# sch_propeller.net
KiCad netlist of a schematic drawn in Altium Designer
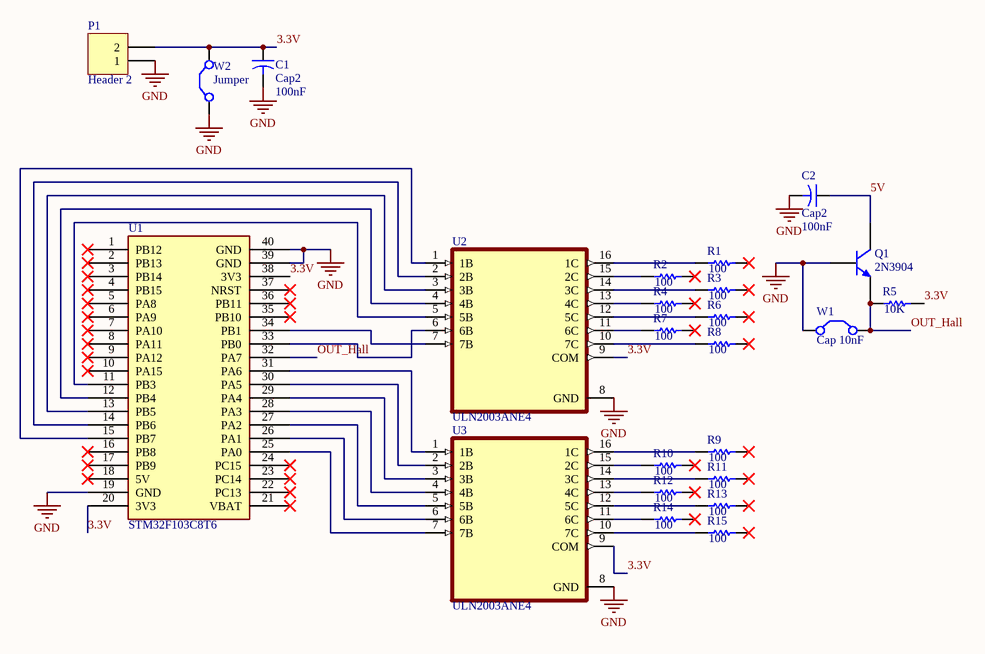
[diagram p0: sch_propeller.SchDoc]

(export (version "E")
  (design (tool "Eeschema 10.0.6"))
  (components
    (comp (ref "C1")
      (value "Cap2")
      (footprint "CAPR5-4X5")
      (description "Capacitor")
      (fields (field (name "ALTIUM_VALUE") "100nF") (field (name "PUBLISHER") "Altium Limited"))
      (libsource (lib "Miscellaneous Devices") (part "Cap2"))
    )
    (comp (ref "C2")
      (value "Cap2")
      (footprint "CAPR5-4X5")
      (description "Capacitor")
      (fields (field (name "ALTIUM_VALUE") "100nF") (field (name "PUBLISHER") "Altium Limited"))
      (libsource (lib "Miscellaneous Devices") (part "Cap2"))
    )
    (comp (ref "P1")
      (value "Header 2")
      (footprint "HDR1X2")
      (description "Header, 2-Pin")
      (fields (field (name "PUBLISHER") "Altium Limited"))
      (libsource (lib "Miscellaneous Connectors") (part "Header 2"))
    )
    (comp (ref "Q1")
      (value "2N3904")
      (footprint "TO-92A")
      (description "NPN General Purpose Amplifier")
      (fields (field (name "PUBLISHER") "Altium Limited"))
      (libsource (lib "Miscellaneous Devices") (part "2N3904"))
    )
    (comp (ref "R1")
      (value "100")
      (footprint "AXIAL-0.3")
      (description "Resistor")
      (fields (field (name "Comment") "Res1") (field (name "PUBLISHER") "Altium Limited"))
      (libsource (lib "Miscellaneous Devices") (part "Res1"))
    )
    (comp (ref "R2")
      (value "100")
      (footprint "AXIAL-0.3")
      (description "Resistor")
      (fields (field (name "Comment") "Res1") (field (name "PUBLISHER") "Altium Limited"))
      (libsource (lib "Miscellaneous Devices") (part "Res1"))
    )
    (comp (ref "R3")
      (value "100")
      (footprint "AXIAL-0.3")
      (description "Resistor")
      (fields (field (name "Comment") "Res1") (field (name "PUBLISHER") "Altium Limited"))
      (libsource (lib "Miscellaneous Devices") (part "Res1"))
    )
    (comp (ref "R4")
      (value "100")
      (footprint "AXIAL-0.3")
      (description "Resistor")
      (fields (field (name "Comment") "Res1") (field (name "PUBLISHER") "Altium Limited"))
      (libsource (lib "Miscellaneous Devices") (part "Res1"))
    )
    (comp (ref "R5")
      (value "10K")
      (footprint "AXIAL-0.3")
      (description "Resistor")
      (fields (field (name "Comment") "Res1") (field (name "PUBLISHER") "Altium Limited"))
      (libsource (lib "Miscellaneous Devices") (part "Res1"))
    )
    (comp (ref "R6")
      (value "100")
      (footprint "AXIAL-0.3")
      (description "Resistor")
      (fields (field (name "Comment") "Res1") (field (name "PUBLISHER") "Altium Limited"))
      (libsource (lib "Miscellaneous Devices") (part "Res1"))
    )
    (comp (ref "R7")
      (value "100")
      (footprint "AXIAL-0.3")
      (description "Resistor")
      (fields (field (name "Comment") "Res1") (field (name "PUBLISHER") "Altium Limited"))
      (libsource (lib "Miscellaneous Devices") (part "Res1"))
    )
    (comp (ref "R8")
      (value "100")
      (footprint "AXIAL-0.3")
      (description "Resistor")
      (fields (field (name "Comment") "Res1") (field (name "PUBLISHER") "Altium Limited"))
      (libsource (lib "Miscellaneous Devices") (part "Res1"))
    )
    (comp (ref "R9")
      (value "100")
      (footprint "AXIAL-0.3")
      (description "Resistor")
      (fields (field (name "Comment") "Res1") (field (name "PUBLISHER") "Altium Limited"))
      (libsource (lib "Miscellaneous Devices") (part "Res1"))
    )
    (comp (ref "R10")
      (value "100")
      (footprint "AXIAL-0.3")
      (description "Resistor")
      (fields (field (name "Comment") "Res1") (field (name "PUBLISHER") "Altium Limited"))
      (libsource (lib "Miscellaneous Devices") (part "Res1"))
    )
    (comp (ref "R11")
      (value "100")
      (footprint "AXIAL-0.3")
      (description "Resistor")
      (fields (field (name "Comment") "Res1") (field (name "PUBLISHER") "Altium Limited"))
      (libsource (lib "Miscellaneous Devices") (part "Res1"))
    )
    (comp (ref "R12")
      (value "100")
      (footprint "AXIAL-0.3")
      (description "Resistor")
      (fields (field (name "Comment") "Res1") (field (name "PUBLISHER") "Altium Limited"))
      (libsource (lib "Miscellaneous Devices") (part "Res1"))
    )
    (comp (ref "R13")
      (value "100")
      (footprint "AXIAL-0.3")
      (description "Resistor")
      (fields (field (name "Comment") "Res1") (field (name "PUBLISHER") "Altium Limited"))
      (libsource (lib "Miscellaneous Devices") (part "Res1"))
    )
    (comp (ref "R14")
      (value "100")
      (footprint "AXIAL-0.3")
      (description "Resistor")
      (fields (field (name "Comment") "Res1") (field (name "PUBLISHER") "Altium Limited"))
      (libsource (lib "Miscellaneous Devices") (part "Res1"))
    )
    (comp (ref "R15")
      (value "100")
      (footprint "AXIAL-0.3")
      (description "Resistor")
      (fields (field (name "Comment") "Res1") (field (name "PUBLISHER") "Altium Limited"))
      (libsource (lib "Miscellaneous Devices") (part "Res1"))
    )
    (comp (ref "U1")
      (value "STM32F103C8T6")
      (footprint "Stm32 BluePill")
      (description "Designed By @Alixahedi")
      (libsource (lib "Stm32 Blue Pill") (part "BluePill"))
    )
    (comp (ref "U2")
      (value "ULN2003ANE4")
      (footprint "DIP794W45P254L1969H508Q16")
      (description "50-V, 7-ch darlington transistor array, -20C to 70C")
      (fields (field (name "MF") "Texas Instruments"))
      (libsource (lib "ULN2003ANE4") (part "ULN2003ANE4"))
    )
    (comp (ref "U3")
      (value "ULN2003ANE4")
      (footprint "DIP794W45P254L1969H508Q16")
      (description "50-V, 7-ch darlington transistor array, -20C to 70C")
      (fields (field (name "MF") "Texas Instruments"))
      (libsource (lib "ULN2003ANE4") (part "ULN2003ANE4"))
    )
    (comp (ref "W1")
      (value "Cap 10nF")
      (footprint "RAD-0.2")
      (description "Jumper Wire")
      (fields (field (name "PUBLISHER") "Altium Limited"))
      (libsource (lib "Miscellaneous Devices") (part "Jumper"))
    )
    (comp (ref "W2")
      (value "Jumper")
      (footprint "RAD-0.2")
      (description "Jumper Wire")
      (fields (field (name "PUBLISHER") "Altium Limited"))
      (libsource (lib "Miscellaneous Devices") (part "Jumper"))
    )
  )
  (nets
    (net (code "1") (name "/3.3V") (class "Default")
      (node (ref "C1") (pin "1") (pinfunction "1_1") (pintype "passive"))
      (node (ref "P1") (pin "2") (pinfunction "2_2") (pintype "passive"))
      (node (ref "R5") (pin "2") (pinfunction "2_2") (pintype "passive"))
      (node (ref "U1") (pin "20") (pinfunction "3V3_20") (pintype "passive"))
      (node (ref "U1") (pin "38") (pinfunction "3V3_38") (pintype "passive"))
      (node (ref "U2") (pin "9") (pinfunction "COM_9") (pintype "output"))
      (node (ref "U3") (pin "9") (pinfunction "COM_9") (pintype "output"))
      (node (ref "W2") (pin "2") (pinfunction "C2_2") (pintype "passive"))
    )
    (net (code "2") (name "/5V") (class "Default")
      (node (ref "C2") (pin "1") (pinfunction "1_1") (pintype "passive"))
      (node (ref "Q1") (pin "3") (pinfunction "C_3") (pintype "passive"))
    )
    (net (code "3") (name "/OUT_Hall") (class "Default")
      (node (ref "Q1") (pin "1") (pinfunction "E_1") (pintype "passive"))
      (node (ref "R5") (pin "1") (pinfunction "1_1") (pintype "passive"))
      (node (ref "U1") (pin "32") (pinfunction "PA7_32") (pintype "passive"))
      (node (ref "W1") (pin "2") (pinfunction "C2_2") (pintype "passive"))
    )
    (net (code "4") (name "GND") (class "Default")
      (node (ref "C1") (pin "2") (pinfunction "2_2") (pintype "passive"))
      (node (ref "C2") (pin "2") (pinfunction "2_2") (pintype "passive"))
      (node (ref "P1") (pin "1") (pinfunction "1_1") (pintype "passive"))
      (node (ref "Q1") (pin "2") (pinfunction "B_2") (pintype "passive"))
      (node (ref "U1") (pin "19") (pinfunction "GND_19") (pintype "passive"))
      (node (ref "U1") (pin "39") (pinfunction "GND_39") (pintype "passive"))
      (node (ref "U1") (pin "40") (pinfunction "GND_40") (pintype "passive"))
      (node (ref "U2") (pin "8") (pinfunction "GND_8") (pintype "power_in"))
      (node (ref "U3") (pin "8") (pinfunction "GND_8") (pintype "power_in"))
      (node (ref "W1") (pin "1") (pinfunction "C1_1") (pintype "passive"))
      (node (ref "W2") (pin "1") (pinfunction "C1_1") (pintype "passive"))
    )
    (net (code "5") (name "Net-(U1-PA0)") (class "Default")
      (node (ref "U1") (pin "25") (pinfunction "PA0_25") (pintype "passive"))
      (node (ref "U3") (pin "7") (pinfunction "7B_7") (pintype "input"))
    )
    (net (code "6") (name "Net-(U1-PA1)") (class "Default")
      (node (ref "U1") (pin "26") (pinfunction "PA1_26") (pintype "passive"))
      (node (ref "U3") (pin "6") (pinfunction "6B_6") (pintype "input"))
    )
    (net (code "7") (name "Net-(U1-PA2)") (class "Default")
      (node (ref "U1") (pin "27") (pinfunction "PA2_27") (pintype "passive"))
      (node (ref "U3") (pin "5") (pinfunction "5B_5") (pintype "input"))
    )
    (net (code "8") (name "Net-(U1-PA3)") (class "Default")
      (node (ref "U1") (pin "28") (pinfunction "PA3_28") (pintype "passive"))
      (node (ref "U3") (pin "4") (pinfunction "4B_4") (pintype "input"))
    )
    (net (code "9") (name "Net-(U1-PA4)") (class "Default")
      (node (ref "U1") (pin "29") (pinfunction "PA4_29") (pintype "passive"))
      (node (ref "U3") (pin "3") (pinfunction "3B_3") (pintype "input"))
    )
    (net (code "10") (name "Net-(U1-PA5)") (class "Default")
      (node (ref "U1") (pin "30") (pinfunction "PA5_30") (pintype "passive"))
      (node (ref "U3") (pin "2") (pinfunction "2B_2") (pintype "input"))
    )
    (net (code "11") (name "Net-(U1-PA6)") (class "Default")
      (node (ref "U1") (pin "31") (pinfunction "PA6_31") (pintype "passive"))
      (node (ref "U3") (pin "1") (pinfunction "1B_1") (pintype "input"))
    )
    (net (code "12") (name "Net-(U1-PB0)") (class "Default")
      (node (ref "U1") (pin "33") (pinfunction "PB0_33") (pintype "passive"))
      (node (ref "U2") (pin "6") (pinfunction "6B_6") (pintype "input"))
    )
    (net (code "13") (name "Net-(U1-PB1)") (class "Default")
      (node (ref "U1") (pin "34") (pinfunction "PB1_34") (pintype "passive"))
      (node (ref "U2") (pin "7") (pinfunction "7B_7") (pintype "input"))
    )
    (net (code "14") (name "Net-(U1-PB3)") (class "Default")
      (node (ref "U1") (pin "11") (pinfunction "PB3_11") (pintype "passive"))
      (node (ref "U2") (pin "5") (pinfunction "5B_5") (pintype "input"))
    )
    (net (code "15") (name "Net-(U1-PB4)") (class "Default")
      (node (ref "U1") (pin "12") (pinfunction "PB4_12") (pintype "passive"))
      (node (ref "U2") (pin "4") (pinfunction "4B_4") (pintype "input"))
    )
    (net (code "16") (name "Net-(U1-PB5)") (class "Default")
      (node (ref "U1") (pin "13") (pinfunction "PB5_13") (pintype "passive"))
      (node (ref "U2") (pin "3") (pinfunction "3B_3") (pintype "input"))
    )
    (net (code "17") (name "Net-(U1-PB6)") (class "Default")
      (node (ref "U1") (pin "14") (pinfunction "PB6_14") (pintype "passive"))
      (node (ref "U2") (pin "2") (pinfunction "2B_2") (pintype "input"))
    )
    (net (code "18") (name "Net-(U1-PB7)") (class "Default")
      (node (ref "U1") (pin "15") (pinfunction "PB7_15") (pintype "passive"))
      (node (ref "U2") (pin "1") (pinfunction "1B_1") (pintype "input"))
    )
    (net (code "19") (name "Net-(U2-1C)") (class "Default")
      (node (ref "R1") (pin "1") (pinfunction "1_1") (pintype "passive"))
      (node (ref "U2") (pin "16") (pinfunction "1C_16") (pintype "output"))
    )
    (net (code "20") (name "Net-(U2-2C)") (class "Default")
      (node (ref "R2") (pin "1") (pinfunction "1_1") (pintype "passive"))
      (node (ref "U2") (pin "15") (pinfunction "2C_15") (pintype "output"))
    )
    (net (code "21") (name "Net-(U2-3C)") (class "Default")
      (node (ref "R3") (pin "1") (pinfunction "1_1") (pintype "passive"))
      (node (ref "U2") (pin "14") (pinfunction "3C_14") (pintype "output"))
    )
    (net (code "22") (name "Net-(U2-4C)") (class "Default")
      (node (ref "R4") (pin "1") (pinfunction "1_1") (pintype "passive"))
      (node (ref "U2") (pin "13") (pinfunction "4C_13") (pintype "output"))
    )
    (net (code "23") (name "Net-(U2-5C)") (class "Default")
      (node (ref "R6") (pin "1") (pinfunction "1_1") (pintype "passive"))
      (node (ref "U2") (pin "12") (pinfunction "5C_12") (pintype "output"))
    )
    (net (code "24") (name "Net-(U2-6C)") (class "Default")
      (node (ref "R7") (pin "1") (pinfunction "1_1") (pintype "passive"))
      (node (ref "U2") (pin "11") (pinfunction "6C_11") (pintype "output"))
    )
    (net (code "25") (name "Net-(U2-7C)") (class "Default")
      (node (ref "R8") (pin "1") (pinfunction "1_1") (pintype "passive"))
      (node (ref "U2") (pin "10") (pinfunction "7C_10") (pintype "output"))
    )
    (net (code "26") (name "Net-(U3-1C)") (class "Default")
      (node (ref "R9") (pin "1") (pinfunction "1_1") (pintype "passive"))
      (node (ref "U3") (pin "16") (pinfunction "1C_16") (pintype "output"))
    )
    (net (code "27") (name "Net-(U3-2C)") (class "Default")
      (node (ref "R10") (pin "1") (pinfunction "1_1") (pintype "passive"))
      (node (ref "U3") (pin "15") (pinfunction "2C_15") (pintype "output"))
    )
    (net (code "28") (name "Net-(U3-3C)") (class "Default")
      (node (ref "R11") (pin "1") (pinfunction "1_1") (pintype "passive"))
      (node (ref "U3") (pin "14") (pinfunction "3C_14") (pintype "output"))
    )
    (net (code "29") (name "Net-(U3-4C)") (class "Default")
      (node (ref "R12") (pin "1") (pinfunction "1_1") (pintype "passive"))
      (node (ref "U3") (pin "13") (pinfunction "4C_13") (pintype "output"))
    )
    (net (code "30") (name "Net-(U3-5C)") (class "Default")
      (node (ref "R13") (pin "1") (pinfunction "1_1") (pintype "passive"))
      (node (ref "U3") (pin "12") (pinfunction "5C_12") (pintype "output"))
    )
    (net (code "31") (name "Net-(U3-6C)") (class "Default")
      (node (ref "R14") (pin "1") (pinfunction "1_1") (pintype "passive"))
      (node (ref "U3") (pin "11") (pinfunction "6C_11") (pintype "output"))
    )
    (net (code "32") (name "Net-(U3-7C)") (class "Default")
      (node (ref "R15") (pin "1") (pinfunction "1_1") (pintype "passive"))
      (node (ref "U3") (pin "10") (pinfunction "7C_10") (pintype "output"))
    )
    (net (code "33") (name "unconnected-(R1-Pad2)") (class "Default")
      (node (ref "R1") (pin "2") (pinfunction "2_2") (pintype "passive+no_connect"))
    )
    (net (code "34") (name "unconnected-(R2-Pad2)") (class "Default")
      (node (ref "R2") (pin "2") (pinfunction "2_2") (pintype "passive+no_connect"))
    )
    (net (code "35") (name "unconnected-(R3-Pad2)") (class "Default")
      (node (ref "R3") (pin "2") (pinfunction "2_2") (pintype "passive+no_connect"))
    )
    (net (code "36") (name "unconnected-(R4-Pad2)") (class "Default")
      (node (ref "R4") (pin "2") (pinfunction "2_2") (pintype "passive+no_connect"))
    )
    (net (code "37") (name "unconnected-(R6-Pad2)") (class "Default")
      (node (ref "R6") (pin "2") (pinfunction "2_2") (pintype "passive+no_connect"))
    )
    (net (code "38") (name "unconnected-(R7-Pad2)") (class "Default")
      (node (ref "R7") (pin "2") (pinfunction "2_2") (pintype "passive+no_connect"))
    )
    (net (code "39") (name "unconnected-(R8-Pad2)") (class "Default")
      (node (ref "R8") (pin "2") (pinfunction "2_2") (pintype "passive+no_connect"))
    )
    (net (code "40") (name "unconnected-(R9-Pad2)") (class "Default")
      (node (ref "R9") (pin "2") (pinfunction "2_2") (pintype "passive+no_connect"))
    )
    (net (code "41") (name "unconnected-(R10-Pad2)") (class "Default")
      (node (ref "R10") (pin "2") (pinfunction "2_2") (pintype "passive+no_connect"))
    )
    (net (code "42") (name "unconnected-(R11-Pad2)") (class "Default")
      (node (ref "R11") (pin "2") (pinfunction "2_2") (pintype "passive+no_connect"))
    )
    (net (code "43") (name "unconnected-(R12-Pad2)") (class "Default")
      (node (ref "R12") (pin "2") (pinfunction "2_2") (pintype "passive+no_connect"))
    )
    (net (code "44") (name "unconnected-(R13-Pad2)") (class "Default")
      (node (ref "R13") (pin "2") (pinfunction "2_2") (pintype "passive+no_connect"))
    )
    (net (code "45") (name "unconnected-(R14-Pad2)") (class "Default")
      (node (ref "R14") (pin "2") (pinfunction "2_2") (pintype "passive+no_connect"))
    )
    (net (code "46") (name "unconnected-(R15-Pad2)") (class "Default")
      (node (ref "R15") (pin "2") (pinfunction "2_2") (pintype "passive+no_connect"))
    )
    (net (code "47") (name "unconnected-(U1-5V-Pad18)") (class "Default")
      (node (ref "U1") (pin "18") (pinfunction "5V_18") (pintype "passive+no_connect"))
    )
    (net (code "48") (name "unconnected-(U1-NRST-Pad37)") (class "Default")
      (node (ref "U1") (pin "37") (pinfunction "NRST_37") (pintype "passive+no_connect"))
    )
    (net (code "49") (name "unconnected-(U1-PA8-Pad5)") (class "Default")
      (node (ref "U1") (pin "5") (pinfunction "PA8_5") (pintype "passive+no_connect"))
    )
    (net (code "50") (name "unconnected-(U1-PA9-Pad6)") (class "Default")
      (node (ref "U1") (pin "6") (pinfunction "PA9_6") (pintype "passive+no_connect"))
    )
    (net (code "51") (name "unconnected-(U1-PA10-Pad7)") (class "Default")
      (node (ref "U1") (pin "7") (pinfunction "PA10_7") (pintype "passive+no_connect"))
    )
    (net (code "52") (name "unconnected-(U1-PA11-Pad8)") (class "Default")
      (node (ref "U1") (pin "8") (pinfunction "PA11_8") (pintype "passive+no_connect"))
    )
    (net (code "53") (name "unconnected-(U1-PA12-Pad9)") (class "Default")
      (node (ref "U1") (pin "9") (pinfunction "PA12_9") (pintype "passive+no_connect"))
    )
    (net (code "54") (name "unconnected-(U1-PA15-Pad10)") (class "Default")
      (node (ref "U1") (pin "10") (pinfunction "PA15_10") (pintype "passive+no_connect"))
    )
    (net (code "55") (name "unconnected-(U1-PB8-Pad16)") (class "Default")
      (node (ref "U1") (pin "16") (pinfunction "PB8_16") (pintype "passive+no_connect"))
    )
    (net (code "56") (name "unconnected-(U1-PB9-Pad17)") (class "Default")
      (node (ref "U1") (pin "17") (pinfunction "PB9_17") (pintype "passive+no_connect"))
    )
    (net (code "57") (name "unconnected-(U1-PB10-Pad35)") (class "Default")
      (node (ref "U1") (pin "35") (pinfunction "PB10_35") (pintype "passive+no_connect"))
    )
    (net (code "58") (name "unconnected-(U1-PB11-Pad36)") (class "Default")
      (node (ref "U1") (pin "36") (pinfunction "PB11_36") (pintype "passive+no_connect"))
    )
    (net (code "59") (name "unconnected-(U1-PB12-Pad1)") (class "Default")
      (node (ref "U1") (pin "1") (pinfunction "PB12_1") (pintype "passive+no_connect"))
    )
    (net (code "60") (name "unconnected-(U1-PB13-Pad2)") (class "Default")
      (node (ref "U1") (pin "2") (pinfunction "PB13_2") (pintype "passive+no_connect"))
    )
    (net (code "61") (name "unconnected-(U1-PB14-Pad3)") (class "Default")
      (node (ref "U1") (pin "3") (pinfunction "PB14_3") (pintype "passive+no_connect"))
    )
    (net (code "62") (name "unconnected-(U1-PB15-Pad4)") (class "Default")
      (node (ref "U1") (pin "4") (pinfunction "PB15_4") (pintype "passive+no_connect"))
    )
    (net (code "63") (name "unconnected-(U1-PC13-Pad22)") (class "Default")
      (node (ref "U1") (pin "22") (pinfunction "PC13_22") (pintype "passive+no_connect"))
    )
    (net (code "64") (name "unconnected-(U1-PC14-Pad23)") (class "Default")
      (node (ref "U1") (pin "23") (pinfunction "PC14_23") (pintype "passive+no_connect"))
    )
    (net (code "65") (name "unconnected-(U1-PC15-Pad24)") (class "Default")
      (node (ref "U1") (pin "24") (pinfunction "PC15_24") (pintype "passive+no_connect"))
    )
    (net (code "66") (name "unconnected-(U1-VBAT-Pad21)") (class "Default")
      (node (ref "U1") (pin "21") (pinfunction "VBAT_21") (pintype "passive+no_connect"))
    )
  )
)
